# Sheet1.net
KiCad netlist of a schematic drawn in Altium Designer
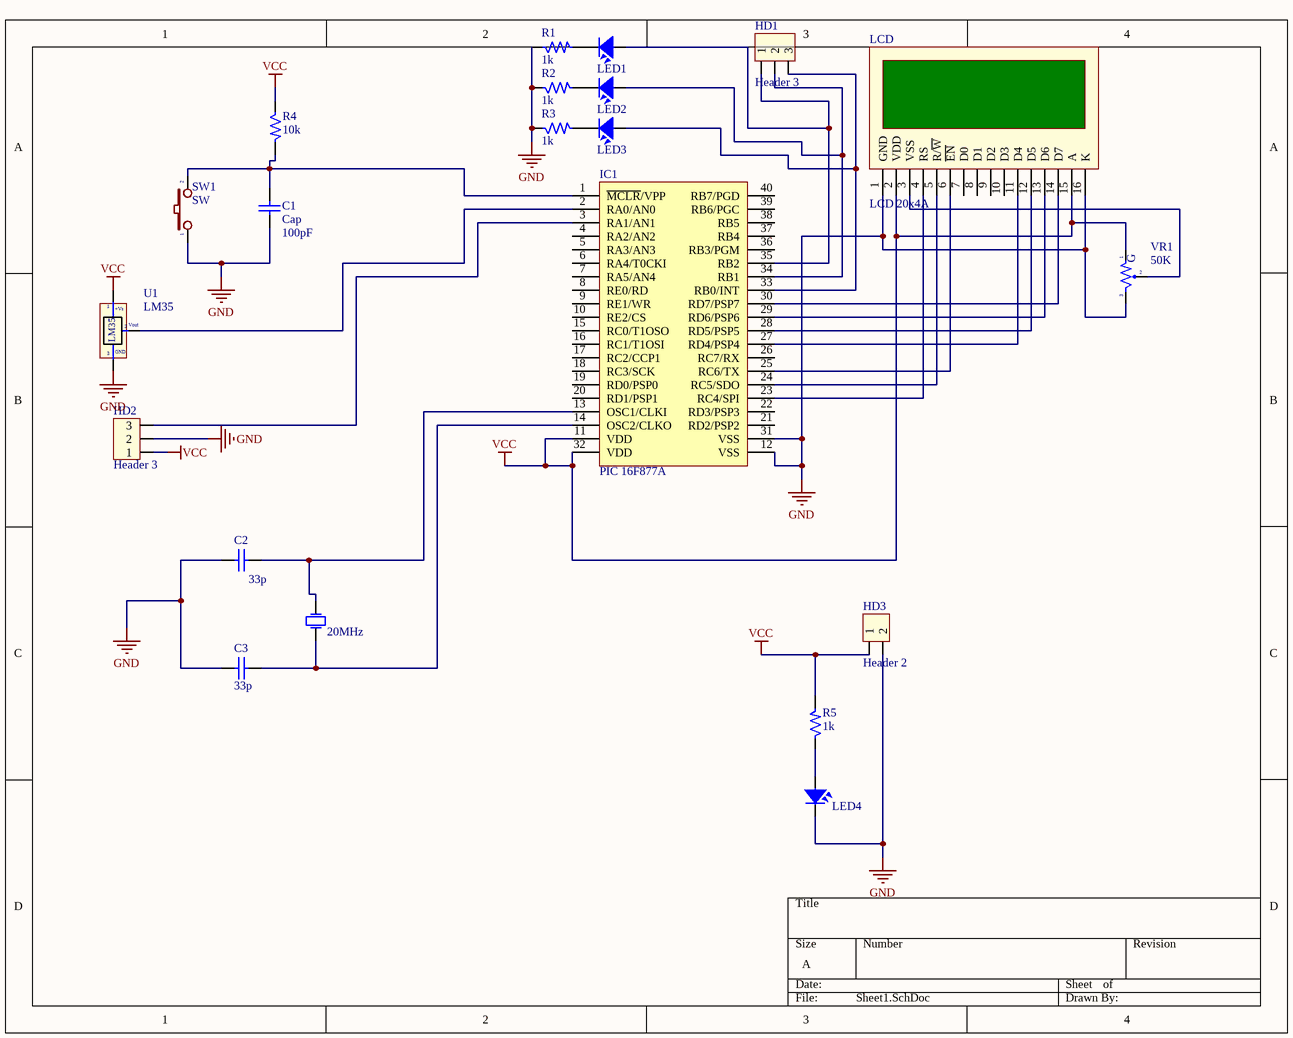
[diagram p0: Sheet1.SchDoc]

(export (version "E")
  (design (tool "Eeschema 10.0.6"))
  (components
    (comp (ref "C1")
      (value "Cap")
      (footprint "RAD-0.3")
      (description "Capacitor")
      (fields (field (name "ALTIUM_VALUE") "100pF") (field (name "PUBLISHER") "Altium Limited"))
      (libsource (lib "Miscellaneous Devices") (part "Cap"))
    )
    (comp (ref "C2")
      (value "33p")
      (footprint "Tu-ceramic")
      (description "Capacitor")
      (fields (field (name "Comment") "Capacitor Ceramic") (field (name "PUBLISHER") "Altium Limited"))
      (libsource (lib "My Library") (part "CapDecop"))
    )
    (comp (ref "C3")
      (value "33p")
      (footprint "Tu-ceramic")
      (description "Capacitor")
      (fields (field (name "Comment") "Capacitor Ceramic") (field (name "PUBLISHER") "Altium Limited"))
      (libsource (lib "My Library") (part "CapDecop"))
    )
    (comp (ref "HD1")
      (value "Header 3")
      (footprint "HED3")
      (description "Header 3 (Green)")
      (libsource (lib "") (part "Hed3_1"))
    )
    (comp (ref "HD2")
      (value "Header 3")
      (footprint "HED3")
      (description "Header 3 (Green)")
      (libsource (lib "syhaunguyen__1") (part "Hed3"))
    )
    (comp (ref "HD3")
      (value "Header 2")
      (footprint "HED2")
      (description "Header 2 (Green)")
      (libsource (lib "syhaunguyen__1") (part "Hed2"))
    )
    (comp (ref "IC1")
      (value "PIC 16F877A")
      (footprint "DIP40/W0.6")
      (description "8K FLASH, 368B RAM, 256B EFROM")
      (fields (field (name "COPYRIGHT BY") "VanDungEvn"))
      (libsource (lib "Library1") (part "PIC16F877-PU"))
    )
    (comp (ref "LCD")
      (value "LCD 20x4A")
      (footprint "LCD20X4A")
      (description "LCD dipslay 20 char, 4 line")
      (libsource (lib "Library1") (part "LCD20x4A"))
    )
    (comp (ref "LED1")
      (value "LED")
      (footprint "LED-3")
      (description "LED Single colour Green and Red")
      (libsource (lib "syhaunguyen__1") (part "LED"))
    )
    (comp (ref "LED2")
      (value "LED")
      (footprint "LED-3")
      (description "LED Single colour Green and Red")
      (libsource (lib "syhaunguyen__1") (part "LED"))
    )
    (comp (ref "LED3")
      (value "LED")
      (footprint "LED-3")
      (description "LED Single colour Green and Red")
      (libsource (lib "syhaunguyen__1") (part "LED"))
    )
    (comp (ref "LED4")
      (value "LED")
      (footprint "LED-3")
      (description "LED Single colour Green and Red")
      (libsource (lib "syhaunguyen__1") (part "LED"))
    )
    (comp (ref "R1")
      (value "1k")
      (footprint "R1/6W")
      (description "Resistor 1/4W")
      (libsource (lib "minhha") (part "Res"))
    )
    (comp (ref "R2")
      (value "1k")
      (footprint "R1/6W")
      (description "Resistor 1/4W")
      (libsource (lib "minhha") (part "Res"))
    )
    (comp (ref "R3")
      (value "1k")
      (footprint "R1/6W")
      (description "Resistor 1/4W")
      (libsource (lib "minhha") (part "Res"))
    )
    (comp (ref "R4")
      (value "10k")
      (footprint "AXIAL-0.5")
      (description "Resistor 1/4W")
      (libsource (lib "My Library") (part "R"))
    )
    (comp (ref "R5")
      (value "1k")
      (footprint "R1/6W")
      (description "Resistor 1/4W")
      (libsource (lib "minhha") (part "Res"))
    )
    (comp (ref "SW1")
      (value "SW")
      (footprint "SW2")
      (description "Switch button 2 pin")
      (libsource (lib "My Library") (part "SW2"))
    )
    (comp (ref "U1")
      (value "LM35")
      (footprint "TO92-123")
      (description "Teminal")
      (libsource (lib "Library1") (part "LM35"))
    )
    (comp (ref "VR1")
      (value "50K")
      (footprint "VR-S1")
      (description "Var Resistor")
      (libsource (lib "Library1") (part "VR-S"))
    )
    (comp (ref "Y1")
      (value "20MHz")
      (footprint "XT2")
      (description "Crystal Oscillator")
      (fields (field (name "PUBLISHER") "Altium Limited"))
      (libsource (lib "minhha") (part "Crystal"))
    )
  )
  (nets
    (net (code "1") (name "GND") (class "Default")
      (node (ref "C1") (pin "1") (pinfunction "1_1") (pintype "passive"))
      (node (ref "C2") (pin "1") (pinfunction "1_1") (pintype "passive"))
      (node (ref "C3") (pin "1") (pinfunction "1_1") (pintype "passive"))
      (node (ref "HD2") (pin "2") (pinfunction "2_2") (pintype "passive"))
      (node (ref "HD3") (pin "2") (pinfunction "2_2") (pintype "passive"))
      (node (ref "IC1") (pin "12") (pinfunction "VSS_12") (pintype "passive"))
      (node (ref "IC1") (pin "31") (pinfunction "VSS_31") (pintype "passive"))
      (node (ref "LCD") (pin "1") (pinfunction "GND_1") (pintype "passive"))
      (node (ref "LCD") (pin "16") (pinfunction "K_16") (pintype "passive"))
      (node (ref "LED4") (pin "2") (pinfunction "2_2") (pintype "passive"))
      (node (ref "R1") (pin "1") (pinfunction "1_1") (pintype "passive"))
      (node (ref "R2") (pin "1") (pinfunction "1_1") (pintype "passive"))
      (node (ref "R3") (pin "1") (pinfunction "1_1") (pintype "passive"))
      (node (ref "SW1") (pin "1") (pinfunction "1_1") (pintype "passive"))
      (node (ref "U1") (pin "3") (pinfunction "-_3") (pintype "passive"))
      (node (ref "VR1") (pin "3") (pinfunction "3_3") (pintype "passive"))
    )
    (net (code "2") (name "Net-(IC1-OSC1{slash}CLKI)") (class "Default")
      (node (ref "C2") (pin "2") (pinfunction "2_2") (pintype "passive"))
      (node (ref "IC1") (pin "13") (pinfunction "OSC1/CLKI_13") (pintype "passive"))
      (node (ref "Y1") (pin "2") (pinfunction "OSC2_2") (pintype "passive"))
    )
    (net (code "3") (name "Net-(IC1-OSC2{slash}CLKO)") (class "Default")
      (node (ref "C3") (pin "2") (pinfunction "2_2") (pintype "passive"))
      (node (ref "IC1") (pin "14") (pinfunction "OSC2/CLKO_14") (pintype "passive"))
      (node (ref "Y1") (pin "1") (pinfunction "OSC1_1") (pintype "passive"))
    )
    (net (code "4") (name "Net-(IC1-RA0{slash}AN0)") (class "Default")
      (node (ref "IC1") (pin "2") (pinfunction "RA0/AN0_2") (pintype "passive"))
      (node (ref "U1") (pin "2") (pinfunction "Vout_2") (pintype "passive"))
    )
    (net (code "5") (name "Net-(IC1-RA1{slash}AN1)") (class "Default")
      (node (ref "HD2") (pin "3") (pinfunction "3_3") (pintype "passive"))
      (node (ref "IC1") (pin "3") (pinfunction "RA1/AN1_3") (pintype "passive"))
    )
    (net (code "6") (name "Net-(IC1-RB0{slash}INT)") (class "Default")
      (node (ref "HD1") (pin "3") (pinfunction "3_3") (pintype "passive"))
      (node (ref "IC1") (pin "33") (pinfunction "RB0/INT_33") (pintype "passive"))
      (node (ref "LED3") (pin "1") (pinfunction "1_1") (pintype "passive"))
    )
    (net (code "7") (name "Net-(IC1-RB1)") (class "Default")
      (node (ref "HD1") (pin "2") (pinfunction "2_2") (pintype "passive"))
      (node (ref "IC1") (pin "34") (pinfunction "RB1_34") (pintype "passive"))
      (node (ref "LED2") (pin "1") (pinfunction "1_1") (pintype "passive"))
    )
    (net (code "8") (name "Net-(IC1-RB2)") (class "Default")
      (node (ref "HD1") (pin "1") (pinfunction "1_1") (pintype "passive"))
      (node (ref "IC1") (pin "35") (pinfunction "RB2_35") (pintype "passive"))
      (node (ref "LED1") (pin "1") (pinfunction "1_1") (pintype "passive"))
    )
    (net (code "9") (name "Net-(IC1-RC4{slash}SPI)") (class "Default")
      (node (ref "IC1") (pin "23") (pinfunction "RC4/SPI_23") (pintype "passive"))
      (node (ref "LCD") (pin "4") (pinfunction "RS_4") (pintype "passive"))
    )
    (net (code "10") (name "Net-(IC1-RC5{slash}SDO)") (class "Default")
      (node (ref "IC1") (pin "24") (pinfunction "RC5/SDO_24") (pintype "passive"))
      (node (ref "LCD") (pin "5") (pinfunction "R/~{W}_5") (pintype "passive"))
    )
    (net (code "11") (name "Net-(IC1-RC6{slash}TX)") (class "Default")
      (node (ref "IC1") (pin "25") (pinfunction "RC6/TX_25") (pintype "passive"))
      (node (ref "LCD") (pin "6") (pinfunction "~{EN}_6") (pintype "passive"))
    )
    (net (code "12") (name "Net-(IC1-RD4{slash}PSP4)") (class "Default")
      (node (ref "IC1") (pin "27") (pinfunction "RD4/PSP4_27") (pintype "passive"))
      (node (ref "LCD") (pin "11") (pinfunction "D4_11") (pintype "passive"))
    )
    (net (code "13") (name "Net-(IC1-RD5{slash}PSP5)") (class "Default")
      (node (ref "IC1") (pin "28") (pinfunction "RD5/PSP5_28") (pintype "passive"))
      (node (ref "LCD") (pin "12") (pinfunction "D5_12") (pintype "passive"))
    )
    (net (code "14") (name "Net-(IC1-RD6{slash}PSP6)") (class "Default")
      (node (ref "IC1") (pin "29") (pinfunction "RD6/PSP6_29") (pintype "passive"))
      (node (ref "LCD") (pin "13") (pinfunction "D6_13") (pintype "passive"))
    )
    (net (code "15") (name "Net-(IC1-RD7{slash}PSP7)") (class "Default")
      (node (ref "IC1") (pin "30") (pinfunction "RD7/PSP7_30") (pintype "passive"))
      (node (ref "LCD") (pin "14") (pinfunction "D7_14") (pintype "passive"))
    )
    (net (code "16") (name "Net-(IC1-~{MCLR}{slash}VPP)") (class "Default")
      (node (ref "C1") (pin "2") (pinfunction "2_2") (pintype "passive"))
      (node (ref "IC1") (pin "1") (pinfunction "~{MCLR}/VPP_1") (pintype "passive"))
      (node (ref "R4") (pin "2") (pinfunction "2_2") (pintype "passive"))
      (node (ref "SW1") (pin "2") (pinfunction "2_2") (pintype "passive"))
    )
    (net (code "17") (name "Net-(LCD-VSS)") (class "Default")
      (node (ref "LCD") (pin "3") (pinfunction "VSS_3") (pintype "passive"))
      (node (ref "VR1") (pin "2") (pinfunction "2_2") (pintype "passive"))
    )
    (net (code "18") (name "Net-(LED1-Pad2)") (class "Default")
      (node (ref "LED1") (pin "2") (pinfunction "2_2") (pintype "passive"))
      (node (ref "R1") (pin "2") (pinfunction "2_2") (pintype "passive"))
    )
    (net (code "19") (name "Net-(LED2-Pad2)") (class "Default")
      (node (ref "LED2") (pin "2") (pinfunction "2_2") (pintype "passive"))
      (node (ref "R2") (pin "2") (pinfunction "2_2") (pintype "passive"))
    )
    (net (code "20") (name "Net-(LED3-Pad2)") (class "Default")
      (node (ref "LED3") (pin "2") (pinfunction "2_2") (pintype "passive"))
      (node (ref "R3") (pin "2") (pinfunction "2_2") (pintype "passive"))
    )
    (net (code "21") (name "Net-(LED4-Pad1)") (class "Default")
      (node (ref "LED4") (pin "1") (pinfunction "1_1") (pintype "passive"))
      (node (ref "R5") (pin "1") (pinfunction "1_1") (pintype "passive"))
    )
    (net (code "22") (name "VCC") (class "Default")
      (node (ref "HD2") (pin "1") (pinfunction "1_1") (pintype "passive"))
      (node (ref "HD3") (pin "1") (pinfunction "1_1") (pintype "passive"))
      (node (ref "IC1") (pin "11") (pinfunction "VDD_11") (pintype "passive"))
      (node (ref "IC1") (pin "32") (pinfunction "VDD_32") (pintype "passive"))
      (node (ref "LCD") (pin "15") (pinfunction "A_15") (pintype "passive"))
      (node (ref "LCD") (pin "2") (pinfunction "VDD_2") (pintype "passive"))
      (node (ref "R4") (pin "1") (pinfunction "1_1") (pintype "passive"))
      (node (ref "R5") (pin "2") (pinfunction "2_2") (pintype "passive"))
      (node (ref "U1") (pin "1") (pinfunction "+Vs_1") (pintype "passive"))
      (node (ref "VR1") (pin "1") (pinfunction "1_1") (pintype "passive"))
    )
    (net (code "23") (name "unconnected-(IC1-RA2{slash}AN2-Pad4)") (class "Default")
      (node (ref "IC1") (pin "4") (pinfunction "RA2/AN2_4") (pintype "passive"))
    )
    (net (code "24") (name "unconnected-(IC1-RA3{slash}AN3-Pad5)") (class "Default")
      (node (ref "IC1") (pin "5") (pinfunction "RA3/AN3_5") (pintype "passive"))
    )
    (net (code "25") (name "unconnected-(IC1-RA4{slash}T0CKI-Pad6)") (class "Default")
      (node (ref "IC1") (pin "6") (pinfunction "RA4/T0CKI_6") (pintype "passive"))
    )
    (net (code "26") (name "unconnected-(IC1-RA5{slash}AN4-Pad7)") (class "Default")
      (node (ref "IC1") (pin "7") (pinfunction "RA5/AN4_7") (pintype "passive"))
    )
    (net (code "27") (name "unconnected-(IC1-RB3{slash}PGM-Pad36)") (class "Default")
      (node (ref "IC1") (pin "36") (pinfunction "RB3/PGM_36") (pintype "passive"))
    )
    (net (code "28") (name "unconnected-(IC1-RB4-Pad37)") (class "Default")
      (node (ref "IC1") (pin "37") (pinfunction "RB4_37") (pintype "passive"))
    )
    (net (code "29") (name "unconnected-(IC1-RB5-Pad38)") (class "Default")
      (node (ref "IC1") (pin "38") (pinfunction "RB5_38") (pintype "passive"))
    )
    (net (code "30") (name "unconnected-(IC1-RB6{slash}PGC-Pad39)") (class "Default")
      (node (ref "IC1") (pin "39") (pinfunction "RB6/PGC_39") (pintype "passive"))
    )
    (net (code "31") (name "unconnected-(IC1-RB7{slash}PGD-Pad40)") (class "Default")
      (node (ref "IC1") (pin "40") (pinfunction "RB7/PGD_40") (pintype "passive"))
    )
    (net (code "32") (name "unconnected-(IC1-RC0{slash}T1OSO-Pad15)") (class "Default")
      (node (ref "IC1") (pin "15") (pinfunction "RC0/T1OSO_15") (pintype "passive"))
    )
    (net (code "33") (name "unconnected-(IC1-RC1{slash}T1OSI-Pad16)") (class "Default")
      (node (ref "IC1") (pin "16") (pinfunction "RC1/T1OSI_16") (pintype "passive"))
    )
    (net (code "34") (name "unconnected-(IC1-RC2{slash}CCP1-Pad17)") (class "Default")
      (node (ref "IC1") (pin "17") (pinfunction "RC2/CCP1_17") (pintype "passive"))
    )
    (net (code "35") (name "unconnected-(IC1-RC3{slash}SCK-Pad18)") (class "Default")
      (node (ref "IC1") (pin "18") (pinfunction "RC3/SCK_18") (pintype "passive"))
    )
    (net (code "36") (name "unconnected-(IC1-RC7{slash}RX-Pad26)") (class "Default")
      (node (ref "IC1") (pin "26") (pinfunction "RC7/RX_26") (pintype "passive"))
    )
    (net (code "37") (name "unconnected-(IC1-RD0{slash}PSP0-Pad19)") (class "Default")
      (node (ref "IC1") (pin "19") (pinfunction "RD0/PSP0_19") (pintype "passive"))
    )
    (net (code "38") (name "unconnected-(IC1-RD1{slash}PSP1-Pad20)") (class "Default")
      (node (ref "IC1") (pin "20") (pinfunction "RD1/PSP1_20") (pintype "passive"))
    )
    (net (code "39") (name "unconnected-(IC1-RD2{slash}PSP2-Pad21)") (class "Default")
      (node (ref "IC1") (pin "21") (pinfunction "RD2/PSP2_21") (pintype "passive"))
    )
    (net (code "40") (name "unconnected-(IC1-RD3{slash}PSP3-Pad22)") (class "Default")
      (node (ref "IC1") (pin "22") (pinfunction "RD3/PSP3_22") (pintype "passive"))
    )
    (net (code "41") (name "unconnected-(IC1-RE0{slash}RD-Pad8)") (class "Default")
      (node (ref "IC1") (pin "8") (pinfunction "RE0/RD_8") (pintype "passive"))
    )
    (net (code "42") (name "unconnected-(IC1-RE1{slash}WR-Pad9)") (class "Default")
      (node (ref "IC1") (pin "9") (pinfunction "RE1/WR_9") (pintype "passive"))
    )
    (net (code "43") (name "unconnected-(IC1-RE2{slash}CS-Pad10)") (class "Default")
      (node (ref "IC1") (pin "10") (pinfunction "RE2/CS_10") (pintype "passive"))
    )
    (net (code "44") (name "unconnected-(LCD-D0-Pad7)") (class "Default")
      (node (ref "LCD") (pin "7") (pinfunction "D0_7") (pintype "passive"))
    )
    (net (code "45") (name "unconnected-(LCD-D1-Pad8)") (class "Default")
      (node (ref "LCD") (pin "8") (pinfunction "D1_8") (pintype "passive"))
    )
    (net (code "46") (name "unconnected-(LCD-D2-Pad9)") (class "Default")
      (node (ref "LCD") (pin "9") (pinfunction "D2_9") (pintype "passive"))
    )
    (net (code "47") (name "unconnected-(LCD-D3-Pad10)") (class "Default")
      (node (ref "LCD") (pin "10") (pinfunction "D3_10") (pintype "passive"))
    )
  )
)
